# tracking-mode-analog-design.net
KiCad netlist of a schematic drawn in EAGLE
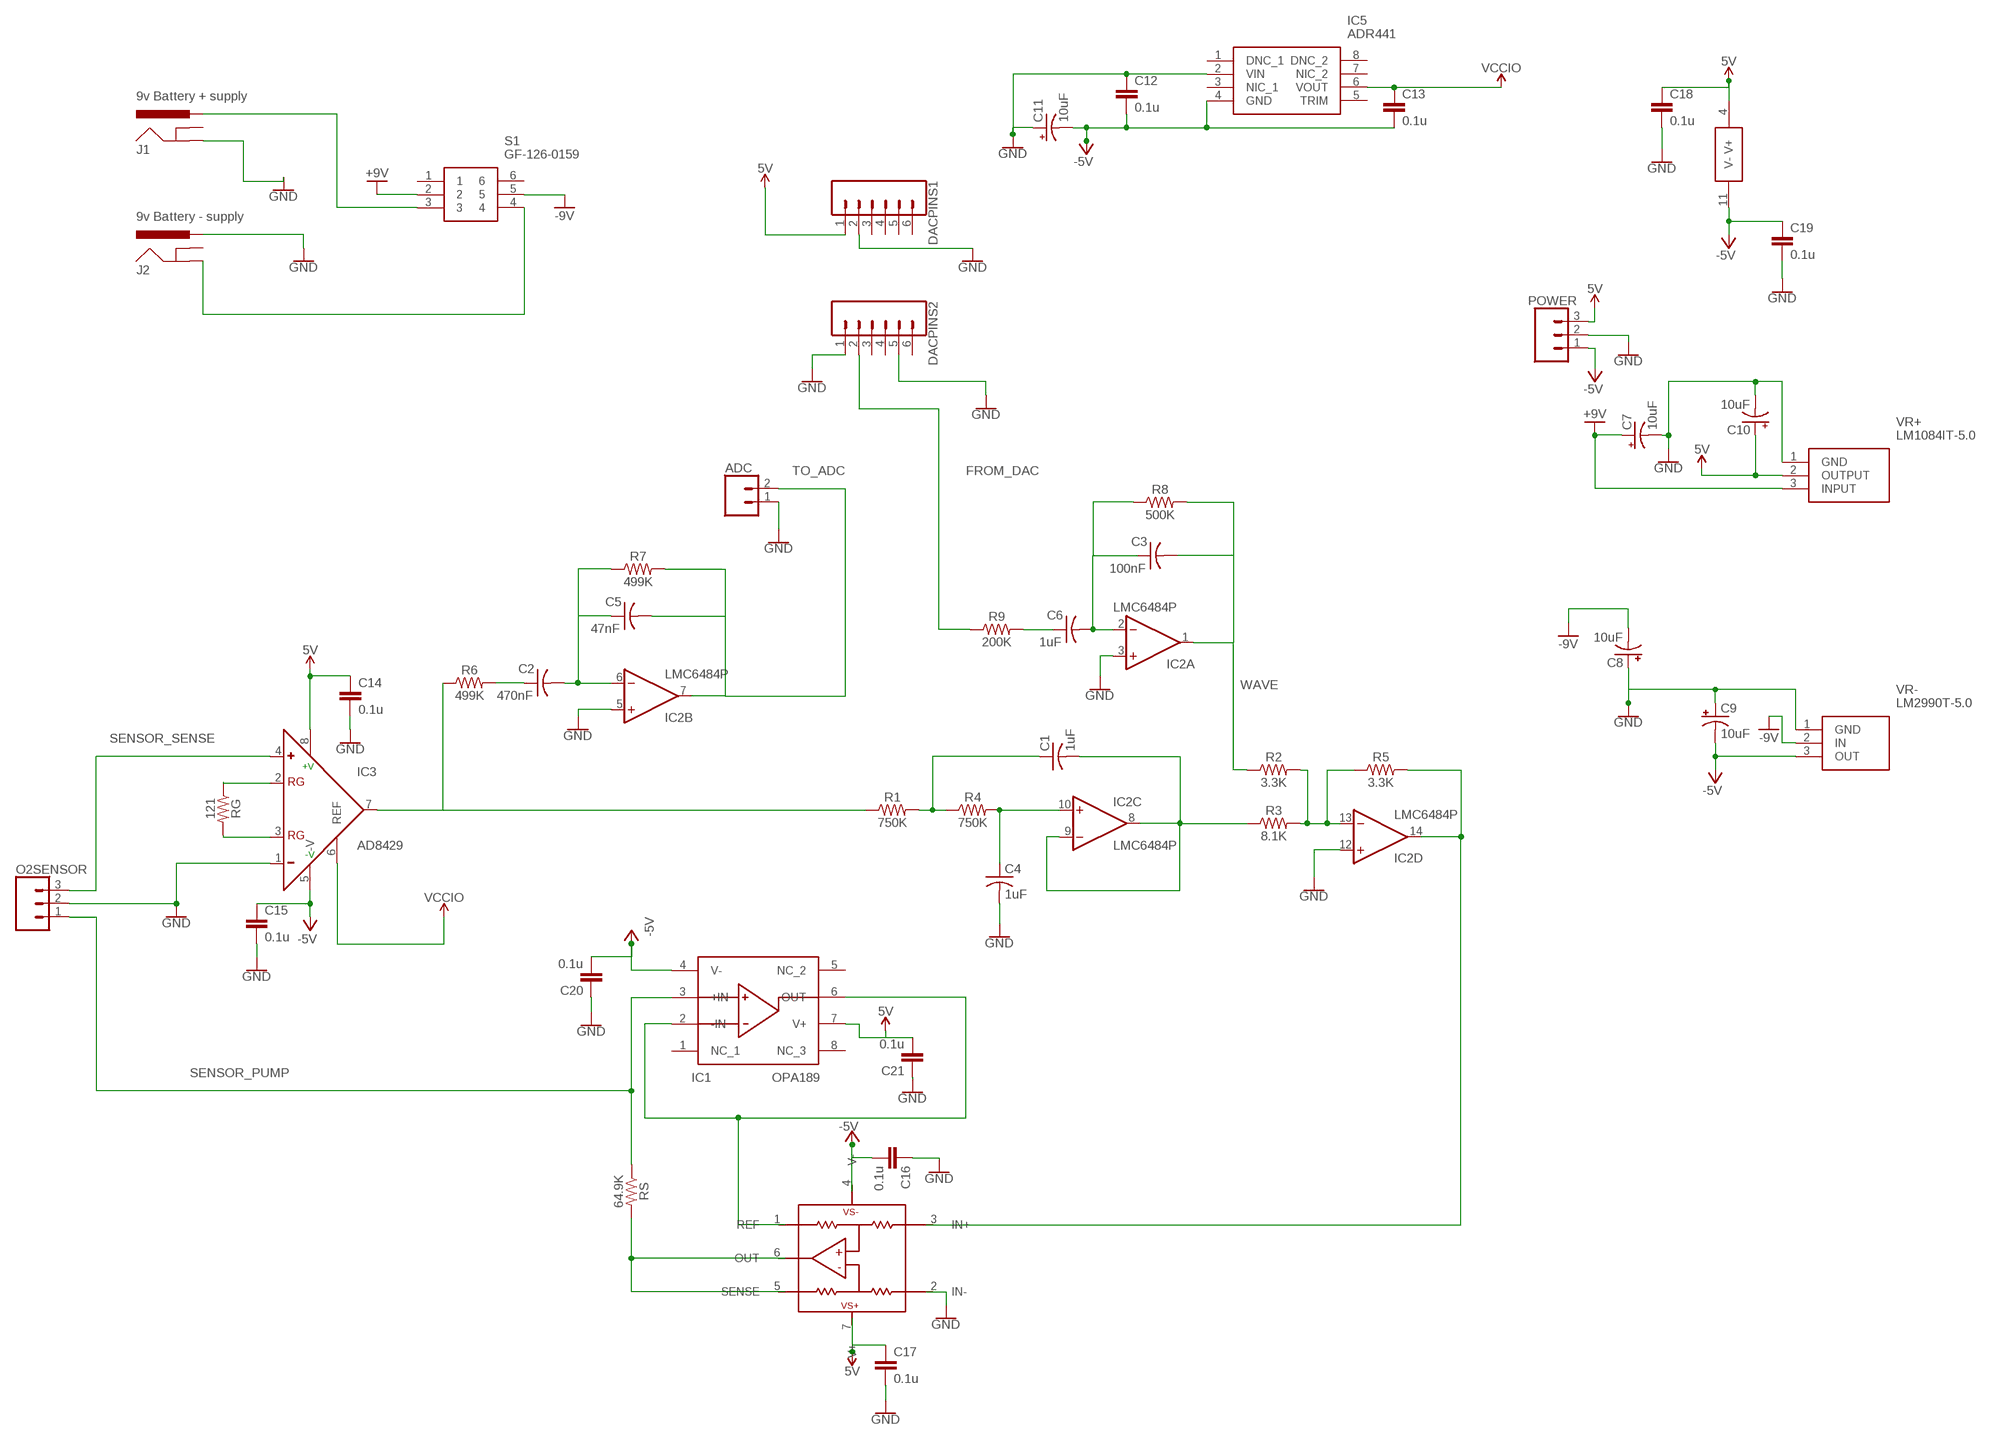
[diagram p0: schematic, sheet 1]

(export (version "E")
  (design (tool "Eeschema 10.0.6"))
  (components
    (comp (ref "ADC")
      (value "CONN_02")
      (footprint "eagle-import:1X02")
      (libsource (lib "eagle-import") (part "CONN_02"))
    )
    (comp (ref "C1")
      (value "1uF")
      (footprint "eagle-import:C025-030X050")
      (libsource (lib "eagle-import") (part "C-US025-030X050"))
    )
    (comp (ref "C2")
      (value "470nF")
      (footprint "eagle-import:C025-030X050")
      (libsource (lib "eagle-import") (part "C-US025-030X050"))
    )
    (comp (ref "C3")
      (value "100nF")
      (footprint "eagle-import:C025-030X050")
      (libsource (lib "eagle-import") (part "C-US025-030X050"))
    )
    (comp (ref "C4")
      (value "1uF")
      (footprint "eagle-import:C025-030X050")
      (libsource (lib "eagle-import") (part "C-US025-030X050"))
    )
    (comp (ref "C5")
      (value "47nF")
      (footprint "eagle-import:C025-030X050")
      (libsource (lib "eagle-import") (part "C-US025-030X050"))
    )
    (comp (ref "C6")
      (value "1uF")
      (footprint "eagle-import:C025-030X050")
      (libsource (lib "eagle-import") (part "C-US025-030X050"))
    )
    (comp (ref "C7")
      (value "10uF")
      (footprint "eagle-import:CPOL-RADIAL-2.5MM-5MM-KIT")
      (libsource (lib "eagle-import") (part "10UF-POLAR-RADIAL-2.5MM-KIT-25V-20%"))
    )
    (comp (ref "C8")
      (value "10uF")
      (footprint "eagle-import:CPOL-RADIAL-2.5MM-5MM-KIT")
      (libsource (lib "eagle-import") (part "10UF-POLAR-RADIAL-2.5MM-KIT-25V-20%"))
    )
    (comp (ref "C9")
      (value "10uF")
      (footprint "eagle-import:CPOL-RADIAL-2.5MM-5MM-KIT")
      (libsource (lib "eagle-import") (part "10UF-POLAR-RADIAL-2.5MM-KIT-25V-20%"))
    )
    (comp (ref "C10")
      (value "10uF")
      (footprint "eagle-import:CPOL-RADIAL-2.5MM-5MM-KIT")
      (libsource (lib "eagle-import") (part "10UF-POLAR-RADIAL-2.5MM-KIT-25V-20%"))
    )
    (comp (ref "C11")
      (value "10uF")
      (footprint "eagle-import:CPOL-RADIAL-2.5MM-5MM-KIT")
      (libsource (lib "eagle-import") (part "10UF-POLAR-RADIAL-2.5MM-KIT-25V-20%"))
    )
    (comp (ref "C12")
      (value "0.1u")
      (footprint "eagle-import:C025-040X050")
      (libsource (lib "eagle-import") (part "C-EU025-040X050"))
    )
    (comp (ref "C13")
      (value "0.1u")
      (footprint "eagle-import:C025-040X050")
      (libsource (lib "eagle-import") (part "C-EU025-040X050"))
    )
    (comp (ref "C14")
      (value "0.1u")
      (footprint "eagle-import:C025-040X050")
      (libsource (lib "eagle-import") (part "C-EU025-040X050"))
    )
    (comp (ref "C15")
      (value "0.1u")
      (footprint "eagle-import:C025-040X050")
      (libsource (lib "eagle-import") (part "C-EU025-040X050"))
    )
    (comp (ref "C16")
      (value "0.1u")
      (footprint "eagle-import:C025-040X050")
      (libsource (lib "eagle-import") (part "C-EU025-040X050"))
    )
    (comp (ref "C17")
      (value "0.1u")
      (footprint "eagle-import:C025-040X050")
      (libsource (lib "eagle-import") (part "C-EU025-040X050"))
    )
    (comp (ref "C18")
      (value "0.1u")
      (footprint "eagle-import:C025-040X050")
      (libsource (lib "eagle-import") (part "C-EU025-040X050"))
    )
    (comp (ref "C19")
      (value "0.1u")
      (footprint "eagle-import:C025-040X050")
      (libsource (lib "eagle-import") (part "C-EU025-040X050"))
    )
    (comp (ref "C20")
      (value "0.1u")
      (footprint "eagle-import:C025-040X050")
      (libsource (lib "eagle-import") (part "C-EU025-040X050"))
    )
    (comp (ref "C21")
      (value "0.1u")
      (footprint "eagle-import:C025-040X050")
      (libsource (lib "eagle-import") (part "C-EU025-040X050"))
    )
    (comp (ref "DACPINS1")
      (value "CONN_06SILK_FEMALE_PTH")
      (footprint "eagle-import:1X06")
      (libsource (lib "eagle-import") (part "CONN_06SILK_FEMALE_PTH"))
    )
    (comp (ref "DACPINS2")
      (value "CONN_06SILK_FEMALE_PTH")
      (footprint "eagle-import:1X06")
      (libsource (lib "eagle-import") (part "CONN_06SILK_FEMALE_PTH"))
    )
    (comp (ref "IC1")
      (value "OPA189")
      (footprint "eagle-import:SOIC127P600X175-8N")
      (fields
        (field (name "MANUFACTURER_PART_NUMBER") "OPA189ID")
        (field (name "MOUSER_PART_NUMBER") "595-OPA189ID")
      )
      (libsource (lib "eagle-import") (part "OPA189ID"))
    )
    (comp (ref "IC2")
      (value "LMC6484P")
      (footprint "eagle-import:DIL14")
      (libsource (lib "eagle-import") (part "LMC6484P"))
    )
    (comp (ref "IC3")
      (value "AD8429")
      (footprint "eagle-import:SO8")
      (fields (field (name "MPN") "AD620AR"))
      (libsource (lib "eagle-import") (part "AD8429R"))
    )
    (comp (ref "IC5")
      (value "ADR441")
      (footprint "eagle-import:SOIC127P600X175-8N")
      (fields
        (field (name "MANUFACTURER_PART_NUMBER") "ADR441ARZ")
        (field (name "MOUSER_PART_NUMBER") "584-ADR441ARZ")
      )
      (libsource (lib "eagle-import") (part "ADR441ARZ"))
    )
    (comp (ref "INA592")
      (value "INA592")
      (footprint "eagle-import:SO08")
      (libsource (lib "eagle-import") (part "INA592"))
    )
    (comp (ref "J1")
      (value "9v Battery + supply")
      (footprint "eagle-import:POWER_JACK_PTH_BREAD")
      (libsource (lib "eagle-import") (part "POWER_JACKPTH_BREAD"))
    )
    (comp (ref "J2")
      (value "9v Battery - supply")
      (footprint "eagle-import:POWER_JACK_PTH_BREAD")
      (libsource (lib "eagle-import") (part "POWER_JACKPTH_BREAD"))
    )
    (comp (ref "O2SENSOR")
      (value "CONN_03")
      (footprint "eagle-import:1X03")
      (libsource (lib "eagle-import") (part "CONN_03"))
    )
    (comp (ref "POWER")
      (value "CONN_03")
      (footprint "eagle-import:1X03")
      (libsource (lib "eagle-import") (part "CONN_03"))
    )
    (comp (ref "R1")
      (value "750K")
      (footprint "eagle-import:AXIAL-0.3")
      (libsource (lib "eagle-import") (part "RESISTORAXIAL-0.3"))
    )
    (comp (ref "R2")
      (value "3.3K")
      (footprint "eagle-import:AXIAL-0.3")
      (libsource (lib "eagle-import") (part "RESISTORAXIAL-0.3"))
    )
    (comp (ref "R3")
      (value "8.1K")
      (footprint "eagle-import:AXIAL-0.3")
      (libsource (lib "eagle-import") (part "RESISTORAXIAL-0.3"))
    )
    (comp (ref "R4")
      (value "750K")
      (footprint "eagle-import:AXIAL-0.3")
      (libsource (lib "eagle-import") (part "RESISTORAXIAL-0.3"))
    )
    (comp (ref "R5")
      (value "3.3K")
      (footprint "eagle-import:AXIAL-0.3")
      (libsource (lib "eagle-import") (part "RESISTORAXIAL-0.3"))
    )
    (comp (ref "R6")
      (value "499K")
      (footprint "eagle-import:AXIAL-0.3")
      (libsource (lib "eagle-import") (part "RESISTORAXIAL-0.3"))
    )
    (comp (ref "R7")
      (value "499K")
      (footprint "eagle-import:AXIAL-0.3")
      (libsource (lib "eagle-import") (part "RESISTORAXIAL-0.3"))
    )
    (comp (ref "R8")
      (value "500K")
      (footprint "eagle-import:AXIAL-0.3")
      (libsource (lib "eagle-import") (part "RESISTORAXIAL-0.3"))
    )
    (comp (ref "R9")
      (value "200K")
      (footprint "eagle-import:AXIAL-0.3")
      (libsource (lib "eagle-import") (part "RESISTORAXIAL-0.3"))
    )
    (comp (ref "RG")
      (value "121")
      (footprint "eagle-import:AXIAL-0.3")
      (libsource (lib "eagle-import") (part "RESISTORAXIAL-0.3"))
    )
    (comp (ref "RS")
      (value "64.9K")
      (footprint "eagle-import:AXIAL-0.3")
      (libsource (lib "eagle-import") (part "RESISTORAXIAL-0.3"))
    )
    (comp (ref "S1")
      (value "GF-126-0159")
      (footprint "eagle-import:GF1260159")
      (fields (field (name "MOUSER_PART_NUMBER") "629-GF1260159"))
      (libsource (lib "eagle-import") (part "GF-126-0159"))
    )
    (comp (ref "VR+")
      (value "LM1084IT-5.0")
      (footprint "eagle-import:TO254P470X1028X1955-3P")
      (fields
        (field (name "MANUFACTURER_PART_NUMBER") "LM1084IT-5.0/NOPB")
        (field (name "MOUSER_PART_NUMBER") "926-LM1084IT50NOPB")
      )
      (libsource (lib "eagle-import") (part "LM1084IT-5.0_NOPB"))
    )
    (comp (ref "VR-")
      (value "LM2990T-5.0")
      (footprint "eagle-import:TO254P470X1028X1955-3P")
      (fields
        (field (name "MANUFACTURER_PART_NUMBER") "LM2990T-5.0/NOPB")
        (field (name "MOUSER_PART_NUMBER") "926-LM2990T-5.0/NOPB")
      )
      (libsource (lib "eagle-import") (part "LM2990T-5.0_NOPB"))
    )
  )
  (nets
    (net (code "1") (name "+9V") (class "Default")
      (node (ref "C7") (pin "1") (pinfunction "+_1") (pintype "passive"))
      (node (ref "S1") (pin "2") (pinfunction "2_2") (pintype "bidirectional"))
      (node (ref "VR+") (pin "3") (pinfunction "INPUT_3") (pintype "input"))
    )
    (net (code "2") (name "-5V") (class "Default")
      (node (ref "C11") (pin "2") (pinfunction "-_2") (pintype "passive"))
      (node (ref "C12") (pin "2") (pinfunction "2_2") (pintype "passive"))
      (node (ref "C13") (pin "2") (pinfunction "2_2") (pintype "passive"))
      (node (ref "C15") (pin "1") (pinfunction "1_1") (pintype "passive"))
      (node (ref "C16") (pin "2") (pinfunction "2_2") (pintype "passive"))
      (node (ref "C19") (pin "1") (pinfunction "1_1") (pintype "passive"))
      (node (ref "C20") (pin "2") (pinfunction "2_2") (pintype "passive"))
      (node (ref "C9") (pin "2") (pinfunction "-_2") (pintype "passive"))
      (node (ref "IC1") (pin "4") (pinfunction "V-_4") (pintype "bidirectional"))
      (node (ref "IC2") (pin "11") (pinfunction "V-_11") (pintype "power_in"))
      (node (ref "IC3") (pin "5") (pinfunction "-V_5") (pintype "power_in"))
      (node (ref "IC5") (pin "4") (pinfunction "GND_4") (pintype "bidirectional"))
      (node (ref "INA592") (pin "4") (pinfunction "V-_4") (pintype "power_in"))
      (node (ref "POWER") (pin "1") (pinfunction "1_1") (pintype "passive"))
      (node (ref "VR-") (pin "3") (pinfunction "OUT_3") (pintype "bidirectional"))
    )
    (net (code "3") (name "-9V") (class "Default")
      (node (ref "C8") (pin "2") (pinfunction "-_2") (pintype "passive"))
      (node (ref "S1") (pin "5") (pinfunction "5_5") (pintype "bidirectional"))
      (node (ref "VR-") (pin "2") (pinfunction "IN_2") (pintype "bidirectional"))
    )
    (net (code "4") (name "/FROM_DAC") (class "Default")
      (node (ref "DACPINS2") (pin "2") (pinfunction "2_2") (pintype "passive"))
      (node (ref "R9") (pin "P$1") (pinfunction "1_P$1") (pintype "passive"))
    )
    (net (code "5") (name "/SENSOR_PUMP") (class "Default")
      (node (ref "IC1") (pin "3") (pinfunction "+IN_3") (pintype "bidirectional"))
      (node (ref "O2SENSOR") (pin "1") (pinfunction "1_1") (pintype "passive"))
      (node (ref "RS") (pin "P$1") (pinfunction "1_P$1") (pintype "passive"))
    )
    (net (code "6") (name "/SENSOR_SENSE") (class "Default")
      (node (ref "IC3") (pin "4") (pinfunction "+_4") (pintype "input"))
      (node (ref "O2SENSOR") (pin "3") (pinfunction "3_3") (pintype "passive"))
    )
    (net (code "7") (name "/TO_ADC") (class "Default")
      (node (ref "ADC") (pin "2") (pinfunction "2_2") (pintype "passive"))
      (node (ref "C5") (pin "2") (pinfunction "2_2") (pintype "passive"))
      (node (ref "IC2") (pin "7") (pinfunction "OUT_7") (pintype "output"))
      (node (ref "R7") (pin "P$2") (pinfunction "2_P$2") (pintype "passive"))
    )
    (net (code "8") (name "/WAVE") (class "Default")
      (node (ref "C3") (pin "2") (pinfunction "2_2") (pintype "passive"))
      (node (ref "IC2") (pin "1") (pinfunction "OUT_1") (pintype "output"))
      (node (ref "R2") (pin "P$1") (pinfunction "1_P$1") (pintype "passive"))
      (node (ref "R8") (pin "P$2") (pinfunction "2_P$2") (pintype "passive"))
    )
    (net (code "9") (name "5V") (class "Default")
      (node (ref "C10") (pin "1") (pinfunction "+_1") (pintype "passive"))
      (node (ref "C14") (pin "1") (pinfunction "1_1") (pintype "passive"))
      (node (ref "C17") (pin "1") (pinfunction "1_1") (pintype "passive"))
      (node (ref "C18") (pin "1") (pinfunction "1_1") (pintype "passive"))
      (node (ref "C21") (pin "2") (pinfunction "2_2") (pintype "passive"))
      (node (ref "DACPINS1") (pin "1") (pinfunction "1_1") (pintype "passive"))
      (node (ref "IC1") (pin "7") (pinfunction "V+_7") (pintype "bidirectional"))
      (node (ref "IC2") (pin "4") (pinfunction "V+_4") (pintype "power_in"))
      (node (ref "IC3") (pin "8") (pinfunction "+V_8") (pintype "power_in"))
      (node (ref "INA592") (pin "7") (pinfunction "V+_7") (pintype "power_in"))
      (node (ref "POWER") (pin "3") (pinfunction "3_3") (pintype "passive"))
      (node (ref "VR+") (pin "2") (pinfunction "OUTPUT_2") (pintype "output"))
    )
    (net (code "10") (name "GND") (class "Default")
      (node (ref "ADC") (pin "1") (pinfunction "1_1") (pintype "passive"))
      (node (ref "C10") (pin "2") (pinfunction "-_2") (pintype "passive"))
      (node (ref "C11") (pin "1") (pinfunction "+_1") (pintype "passive"))
      (node (ref "C12") (pin "1") (pinfunction "1_1") (pintype "passive"))
      (node (ref "C14") (pin "2") (pinfunction "2_2") (pintype "passive"))
      (node (ref "C15") (pin "2") (pinfunction "2_2") (pintype "passive"))
      (node (ref "C16") (pin "1") (pinfunction "1_1") (pintype "passive"))
      (node (ref "C17") (pin "2") (pinfunction "2_2") (pintype "passive"))
      (node (ref "C18") (pin "2") (pinfunction "2_2") (pintype "passive"))
      (node (ref "C19") (pin "2") (pinfunction "2_2") (pintype "passive"))
      (node (ref "C20") (pin "1") (pinfunction "1_1") (pintype "passive"))
      (node (ref "C21") (pin "1") (pinfunction "1_1") (pintype "passive"))
      (node (ref "C4") (pin "2") (pinfunction "2_2") (pintype "passive"))
      (node (ref "C7") (pin "2") (pinfunction "-_2") (pintype "passive"))
      (node (ref "C8") (pin "1") (pinfunction "+_1") (pintype "passive"))
      (node (ref "C9") (pin "1") (pinfunction "+_1") (pintype "passive"))
      (node (ref "DACPINS1") (pin "2") (pinfunction "2_2") (pintype "passive"))
      (node (ref "DACPINS2") (pin "1") (pinfunction "1_1") (pintype "passive"))
      (node (ref "DACPINS2") (pin "5") (pinfunction "5_5") (pintype "passive"))
      (node (ref "IC2") (pin "12") (pinfunction "+IN_12") (pintype "input"))
      (node (ref "IC2") (pin "3") (pinfunction "+IN_3") (pintype "input"))
      (node (ref "IC2") (pin "5") (pinfunction "+IN_5") (pintype "input"))
      (node (ref "IC3") (pin "1") (pinfunction "-_1") (pintype "input"))
      (node (ref "IC5") (pin "2") (pinfunction "VIN_2") (pintype "bidirectional"))
      (node (ref "INA592") (pin "2") (pinfunction "IN-_2") (pintype "input"))
      (node (ref "J1") (pin "GND") (pinfunction "GND_GND") (pintype "bidirectional"))
      (node (ref "J2") (pin "PWR") (pinfunction "PWR_PWR") (pintype "bidirectional"))
      (node (ref "O2SENSOR") (pin "2") (pinfunction "2_2") (pintype "passive"))
      (node (ref "POWER") (pin "2") (pinfunction "2_2") (pintype "passive"))
      (node (ref "VR+") (pin "1") (pinfunction "GND_1") (pintype "power_in"))
      (node (ref "VR-") (pin "1") (pinfunction "GND_1") (pintype "bidirectional"))
    )
    (net (code "11") (name "Net-(IC1--IN)") (class "Default")
      (node (ref "IC1") (pin "2") (pinfunction "-IN_2") (pintype "bidirectional"))
      (node (ref "IC1") (pin "6") (pinfunction "OUT_6") (pintype "bidirectional"))
      (node (ref "INA592") (pin "1") (pinfunction "REF_1") (pintype "input"))
    )
    (net (code "12") (name "Net-(IC2A--IN)") (class "Default")
      (node (ref "C3") (pin "1") (pinfunction "1_1") (pintype "passive"))
      (node (ref "C6") (pin "2") (pinfunction "2_2") (pintype "passive"))
      (node (ref "IC2") (pin "2") (pinfunction "-IN_2") (pintype "input"))
      (node (ref "R8") (pin "P$1") (pinfunction "1_P$1") (pintype "passive"))
    )
    (net (code "13") (name "Net-(IC2B--IN)") (class "Default")
      (node (ref "C2") (pin "2") (pinfunction "2_2") (pintype "passive"))
      (node (ref "C5") (pin "1") (pinfunction "1_1") (pintype "passive"))
      (node (ref "IC2") (pin "6") (pinfunction "-IN_6") (pintype "input"))
      (node (ref "R7") (pin "P$1") (pinfunction "1_P$1") (pintype "passive"))
    )
    (net (code "14") (name "Net-(IC2C-+IN)") (class "Default")
      (node (ref "C4") (pin "1") (pinfunction "1_1") (pintype "passive"))
      (node (ref "IC2") (pin "10") (pinfunction "+IN_10") (pintype "input"))
      (node (ref "R4") (pin "P$2") (pinfunction "2_P$2") (pintype "passive"))
    )
    (net (code "15") (name "Net-(IC2C--IN)") (class "Default")
      (node (ref "C1") (pin "2") (pinfunction "2_2") (pintype "passive"))
      (node (ref "IC2") (pin "8") (pinfunction "OUT_8") (pintype "output"))
      (node (ref "IC2") (pin "9") (pinfunction "-IN_9") (pintype "input"))
      (node (ref "R3") (pin "P$1") (pinfunction "1_P$1") (pintype "passive"))
    )
    (net (code "16") (name "Net-(IC2D--IN)") (class "Default")
      (node (ref "IC2") (pin "13") (pinfunction "-IN_13") (pintype "input"))
      (node (ref "R2") (pin "P$2") (pinfunction "2_P$2") (pintype "passive"))
      (node (ref "R3") (pin "P$2") (pinfunction "2_P$2") (pintype "passive"))
      (node (ref "R5") (pin "P$1") (pinfunction "1_P$1") (pintype "passive"))
    )
    (net (code "17") (name "Net-(IC2D-OUT)") (class "Default")
      (node (ref "IC2") (pin "14") (pinfunction "OUT_14") (pintype "output"))
      (node (ref "INA592") (pin "3") (pinfunction "IN+_3") (pintype "input"))
      (node (ref "R5") (pin "P$2") (pinfunction "2_P$2") (pintype "passive"))
    )
    (net (code "18") (name "Net-(IC3-OUT)") (class "Default")
      (node (ref "IC3") (pin "7") (pinfunction "OUT_7") (pintype "output"))
      (node (ref "R1") (pin "P$1") (pinfunction "1_P$1") (pintype "passive"))
      (node (ref "R6") (pin "P$1") (pinfunction "1_P$1") (pintype "passive"))
    )
    (net (code "19") (name "Net-(INA592-OUT)") (class "Default")
      (node (ref "INA592") (pin "5") (pinfunction "SENSE_5") (pintype "input"))
      (node (ref "INA592") (pin "6") (pinfunction "OUT_6") (pintype "output"))
      (node (ref "RS") (pin "P$2") (pinfunction "2_P$2") (pintype "passive"))
    )
    (net (code "20") (name "Net-(J1-PadPWR)") (class "Default")
      (node (ref "J1") (pin "PWR") (pinfunction "PWR_PWR") (pintype "bidirectional"))
      (node (ref "S1") (pin "3") (pinfunction "3_3") (pintype "bidirectional"))
    )
    (net (code "21") (name "Net-(J2-PadGND)") (class "Default")
      (node (ref "J2") (pin "GND") (pinfunction "GND_GND") (pintype "bidirectional"))
      (node (ref "S1") (pin "4") (pinfunction "4_4") (pintype "bidirectional"))
    )
    (net (code "22") (name "Net-(R1-2)") (class "Default")
      (node (ref "C1") (pin "1") (pinfunction "1_1") (pintype "passive"))
      (node (ref "R1") (pin "P$2") (pinfunction "2_P$2") (pintype "passive"))
      (node (ref "R4") (pin "P$1") (pinfunction "1_P$1") (pintype "passive"))
    )
    (net (code "23") (name "Net-(R6-2)") (class "Default")
      (node (ref "C2") (pin "1") (pinfunction "1_1") (pintype "passive"))
      (node (ref "R6") (pin "P$2") (pinfunction "2_P$2") (pintype "passive"))
    )
    (net (code "24") (name "Net-(R9-2)") (class "Default")
      (node (ref "C6") (pin "1") (pinfunction "1_1") (pintype "passive"))
      (node (ref "R9") (pin "P$2") (pinfunction "2_P$2") (pintype "passive"))
    )
    (net (code "25") (name "Net-(RG-1)") (class "Default")
      (node (ref "IC3") (pin "2") (pinfunction "RG_2") (pintype "passive"))
      (node (ref "RG") (pin "P$1") (pinfunction "1_P$1") (pintype "passive"))
    )
    (net (code "26") (name "Net-(RG-2)") (class "Default")
      (node (ref "IC3") (pin "3") (pinfunction "RG_3") (pintype "passive"))
      (node (ref "RG") (pin "P$2") (pinfunction "2_P$2") (pintype "passive"))
    )
    (net (code "27") (name "VCCIO") (class "Default")
      (node (ref "C13") (pin "1") (pinfunction "1_1") (pintype "passive"))
      (node (ref "IC3") (pin "6") (pinfunction "REF_6") (pintype "passive"))
      (node (ref "IC5") (pin "6") (pinfunction "VOUT_6") (pintype "bidirectional"))
    )
    (net (code "28") (name "unconnected-(DACPINS1-Pad3)") (class "Default")
      (node (ref "DACPINS1") (pin "3") (pinfunction "3_3") (pintype "passive"))
    )
    (net (code "29") (name "unconnected-(DACPINS1-Pad4)") (class "Default")
      (node (ref "DACPINS1") (pin "4") (pinfunction "4_4") (pintype "passive"))
    )
    (net (code "30") (name "unconnected-(DACPINS1-Pad5)") (class "Default")
      (node (ref "DACPINS1") (pin "5") (pinfunction "5_5") (pintype "passive"))
    )
    (net (code "31") (name "unconnected-(DACPINS1-Pad6)") (class "Default")
      (node (ref "DACPINS1") (pin "6") (pinfunction "6_6") (pintype "passive"))
    )
    (net (code "32") (name "unconnected-(DACPINS2-Pad3)") (class "Default")
      (node (ref "DACPINS2") (pin "3") (pinfunction "3_3") (pintype "passive"))
    )
    (net (code "33") (name "unconnected-(DACPINS2-Pad4)") (class "Default")
      (node (ref "DACPINS2") (pin "4") (pinfunction "4_4") (pintype "passive"))
    )
    (net (code "34") (name "unconnected-(DACPINS2-Pad6)") (class "Default")
      (node (ref "DACPINS2") (pin "6") (pinfunction "6_6") (pintype "passive"))
    )
    (net (code "35") (name "unconnected-(IC1-NC_1-Pad1)") (class "Default")
      (node (ref "IC1") (pin "1") (pinfunction "NC_1_1") (pintype "bidirectional"))
    )
    (net (code "36") (name "unconnected-(IC1-NC_2-Pad5)") (class "Default")
      (node (ref "IC1") (pin "5") (pinfunction "NC_2_5") (pintype "bidirectional"))
    )
    (net (code "37") (name "unconnected-(IC1-NC_3-Pad8)") (class "Default")
      (node (ref "IC1") (pin "8") (pinfunction "NC_3_8") (pintype "bidirectional"))
    )
    (net (code "38") (name "unconnected-(IC5-DNC_1-Pad1)") (class "Default")
      (node (ref "IC5") (pin "1") (pinfunction "DNC_1_1") (pintype "bidirectional"))
    )
    (net (code "39") (name "unconnected-(IC5-DNC_2-Pad8)") (class "Default")
      (node (ref "IC5") (pin "8") (pinfunction "DNC_2_8") (pintype "bidirectional"))
    )
    (net (code "40") (name "unconnected-(IC5-NIC_1-Pad3)") (class "Default")
      (node (ref "IC5") (pin "3") (pinfunction "NIC_1_3") (pintype "bidirectional"))
    )
    (net (code "41") (name "unconnected-(IC5-NIC_2-Pad7)") (class "Default")
      (node (ref "IC5") (pin "7") (pinfunction "NIC_2_7") (pintype "bidirectional"))
    )
    (net (code "42") (name "unconnected-(IC5-TRIM-Pad5)") (class "Default")
      (node (ref "IC5") (pin "5") (pinfunction "TRIM_5") (pintype "bidirectional"))
    )
    (net (code "43") (name "unconnected-(J1-PadGNDBREAK)") (class "Default")
      (node (ref "J1") (pin "GNDBREAK") (pinfunction "GNDBREAK_GNDBREAK") (pintype "bidirectional"))
    )
    (net (code "44") (name "unconnected-(J2-PadGNDBREAK)") (class "Default")
      (node (ref "J2") (pin "GNDBREAK") (pinfunction "GNDBREAK_GNDBREAK") (pintype "bidirectional"))
    )
    (net (code "45") (name "unconnected-(S1-Pad1)") (class "Default")
      (node (ref "S1") (pin "1") (pinfunction "1_1") (pintype "bidirectional"))
    )
    (net (code "46") (name "unconnected-(S1-Pad6)") (class "Default")
      (node (ref "S1") (pin "6") (pinfunction "6_6") (pintype "bidirectional"))
    )
  )
)
